# Lightbox.net
KiCad netlist of a schematic drawn in EAGLE
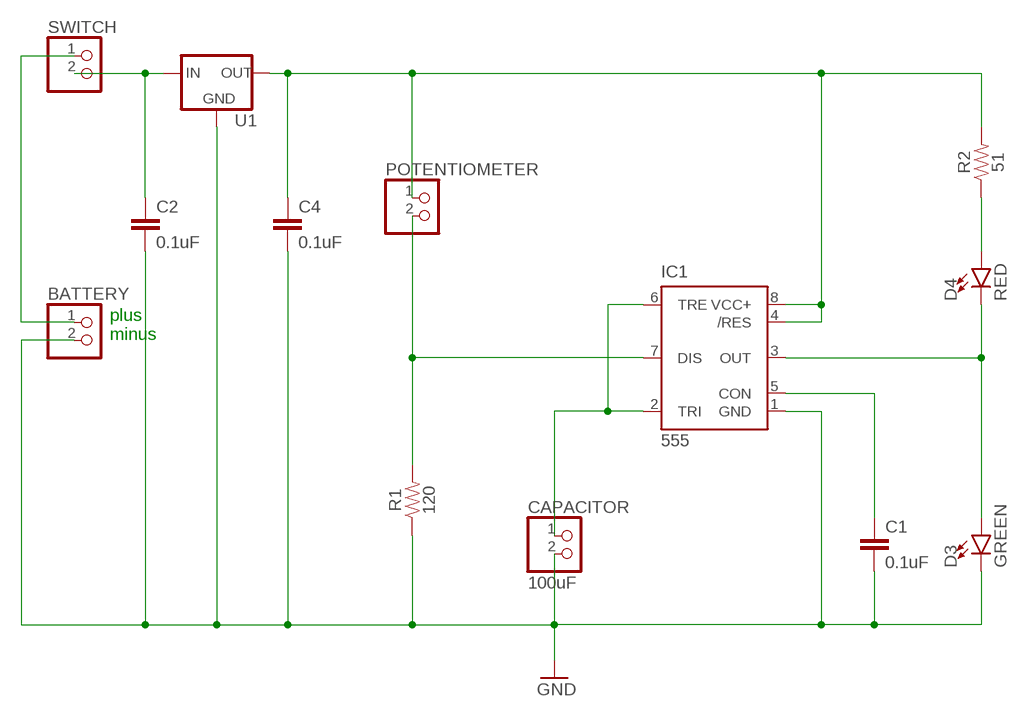
[diagram p0: schematic, sheet 1]

(export (version "E")
  (design (tool "Eeschema 10.0.6"))
  (components
    (comp (ref "BATTERY")
      (value "PINHD-1X2")
      (footprint "eagle-import:1X02")
      (libsource (lib "eagle-import") (part "PINHD-1X2"))
    )
    (comp (ref "C1")
      (value "0.1uF")
      (footprint "eagle-import:0402")
      (libsource (lib "eagle-import") (part "0.1UF-0402-16V-10%"))
    )
    (comp (ref "C2")
      (value "0.1uF")
      (footprint "eagle-import:0402")
      (libsource (lib "eagle-import") (part "0.1UF-0402-16V-10%"))
    )
    (comp (ref "C4")
      (value "0.1uF")
      (footprint "eagle-import:0402")
      (libsource (lib "eagle-import") (part "0.1UF-0402-16V-10%"))
    )
    (comp (ref "CAPACITOR")
      (value "100uF")
      (footprint "eagle-import:1X02")
      (libsource (lib "eagle-import") (part "PINHD-1X2"))
    )
    (comp (ref "D3")
      (value "GREEN")
      (footprint "eagle-import:LED-1206")
      (libsource (lib "eagle-import") (part "LED-GREEN1206"))
    )
    (comp (ref "D4")
      (value "RED")
      (footprint "eagle-import:LED-1206")
      (libsource (lib "eagle-import") (part "LED-RED1206"))
    )
    (comp (ref "IC1")
      (value "555")
      (footprint "eagle-import:DIP08")
      (libsource (lib "eagle-import") (part "555P"))
    )
    (comp (ref "POTENTIOMETER")
      (value "PINHD-1X2")
      (footprint "eagle-import:1X02")
      (libsource (lib "eagle-import") (part "PINHD-1X2"))
    )
    (comp (ref "R1")
      (value "120")
      (footprint "eagle-import:0603")
      (libsource (lib "eagle-import") (part "100OHM-0603-1/4W-5%"))
    )
    (comp (ref "R2")
      (value "51")
      (footprint "eagle-import:0603")
      (libsource (lib "eagle-import") (part "220OHM-0603-1/10W-1%"))
    )
    (comp (ref "SWITCH")
      (value "PINHD-1X2")
      (footprint "eagle-import:1X02")
      (libsource (lib "eagle-import") (part "PINHD-1X2"))
    )
    (comp (ref "U1")
      (value "V_REG_78XX-TO-220")
      (footprint "eagle-import:TO-220-ALT")
      (libsource (lib "eagle-import") (part "V_REG_78XX-TO-220"))
    )
  )
  (nets
    (net (code "1") (name "GND") (class "Default")
      (node (ref "BATTERY") (pin "2") (pinfunction "2_2") (pintype "passive"))
      (node (ref "C1") (pin "2") (pinfunction "2_2") (pintype "passive"))
      (node (ref "C2") (pin "2") (pinfunction "2_2") (pintype "passive"))
      (node (ref "C4") (pin "2") (pinfunction "2_2") (pintype "passive"))
      (node (ref "CAPACITOR") (pin "2") (pinfunction "2_2") (pintype "passive"))
      (node (ref "D3") (pin "C") (pinfunction "C_C") (pintype "passive"))
      (node (ref "IC1") (pin "1") (pinfunction "GND_1") (pintype "power_in"))
      (node (ref "R1") (pin "1") (pinfunction "1_1") (pintype "passive"))
      (node (ref "U1") (pin "GND") (pinfunction "GND_GND") (pintype "input"))
    )
    (net (code "2") (name "Net-(BATTERY-Pad1)") (class "Default")
      (node (ref "BATTERY") (pin "1") (pinfunction "1_1") (pintype "passive"))
      (node (ref "SWITCH") (pin "1") (pinfunction "1_1") (pintype "passive"))
    )
    (net (code "3") (name "Net-(C2-Pad1)") (class "Default")
      (node (ref "C2") (pin "1") (pinfunction "1_1") (pintype "passive"))
      (node (ref "SWITCH") (pin "2") (pinfunction "2_2") (pintype "passive"))
      (node (ref "U1") (pin "IN") (pinfunction "IN_IN") (pintype "input"))
    )
    (net (code "4") (name "Net-(D4-PadA)") (class "Default")
      (node (ref "D4") (pin "A") (pinfunction "A_A") (pintype "passive"))
      (node (ref "R2") (pin "1") (pinfunction "1_1") (pintype "passive"))
    )
    (net (code "5") (name "Net-(IC1-CON)") (class "Default")
      (node (ref "C1") (pin "1") (pinfunction "1_1") (pintype "passive"))
      (node (ref "IC1") (pin "5") (pinfunction "CON_5") (pintype "input"))
    )
    (net (code "6") (name "Net-(IC1-DIS)") (class "Default")
      (node (ref "IC1") (pin "7") (pinfunction "DIS_7") (pintype "input"))
      (node (ref "POTENTIOMETER") (pin "2") (pinfunction "2_2") (pintype "passive"))
      (node (ref "R1") (pin "2") (pinfunction "2_2") (pintype "passive"))
    )
    (net (code "7") (name "Net-(IC1-OUT)") (class "Default")
      (node (ref "D3") (pin "A") (pinfunction "A_A") (pintype "passive"))
      (node (ref "D4") (pin "C") (pinfunction "C_C") (pintype "passive"))
      (node (ref "IC1") (pin "3") (pinfunction "OUT_3") (pintype "output"))
    )
    (net (code "8") (name "Net-(IC1-TRE)") (class "Default")
      (node (ref "CAPACITOR") (pin "1") (pinfunction "1_1") (pintype "passive"))
      (node (ref "IC1") (pin "2") (pinfunction "TRI_2") (pintype "input"))
      (node (ref "IC1") (pin "6") (pinfunction "TRE_6") (pintype "input"))
    )
    (net (code "9") (name "Net-(IC1-VCC+)") (class "Default")
      (node (ref "C4") (pin "1") (pinfunction "1_1") (pintype "passive"))
      (node (ref "IC1") (pin "4") (pinfunction "/RES_4") (pintype "input"))
      (node (ref "IC1") (pin "8") (pinfunction "VCC+_8") (pintype "power_in"))
      (node (ref "POTENTIOMETER") (pin "1") (pinfunction "1_1") (pintype "passive"))
      (node (ref "R2") (pin "2") (pinfunction "2_2") (pintype "passive"))
      (node (ref "U1") (pin "OUT") (pinfunction "OUT_OUT") (pintype "passive"))
    )
  )
)
